# HandTieSchematic.net
KiCad netlist of a schematic drawn in Altium Designer
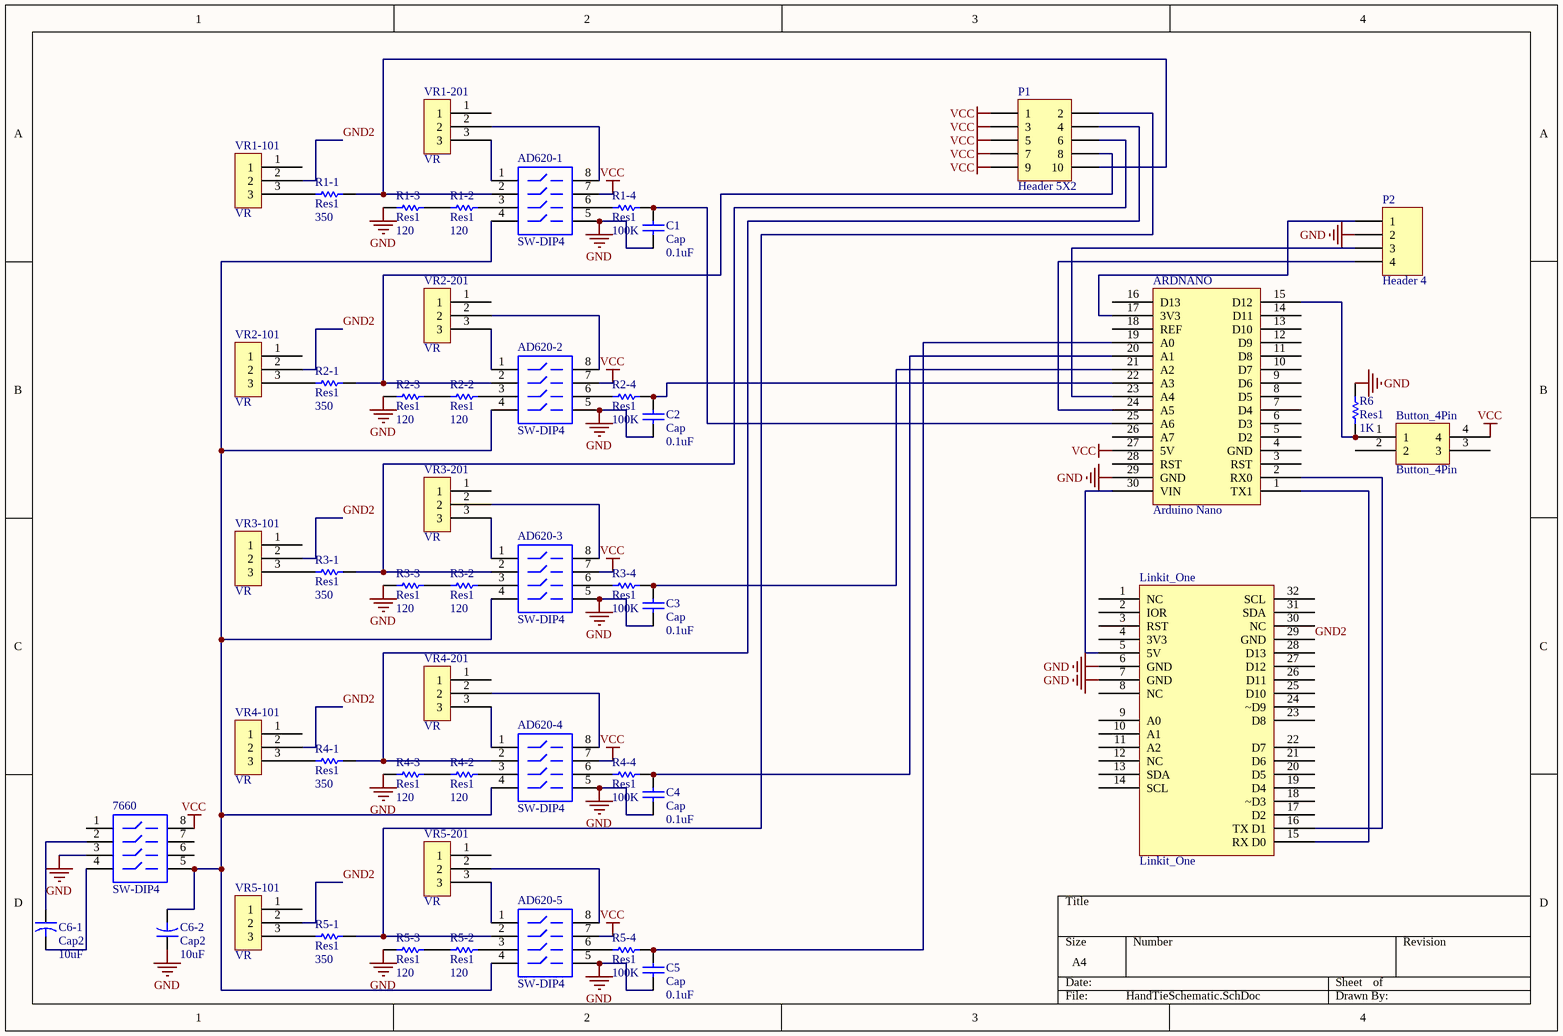
[diagram p0: HandTieSchematic.SchDoc]

(export (version "E")
  (design (tool "Eeschema 10.0.6"))
  (components
    (comp (ref "7660")
      (value "SW-DIP4")
      (footprint "DIP-8")
      (description "DIP Switch")
      (fields (field (name "PUBLISHER") "Altium Limited"))
      (libsource (lib "Miscellaneous Devices") (part "SW-DIP4"))
    )
    (comp (ref "AD620-1")
      (value "SW-DIP4")
      (footprint "DIP-8")
      (description "DIP Switch")
      (fields (field (name "PUBLISHER") "Altium Limited"))
      (libsource (lib "Miscellaneous Devices") (part "SW-DIP4"))
    )
    (comp (ref "AD620-2")
      (value "SW-DIP4")
      (footprint "DIP-8")
      (description "DIP Switch")
      (fields (field (name "PUBLISHER") "Altium Limited"))
      (libsource (lib "Miscellaneous Devices") (part "SW-DIP4"))
    )
    (comp (ref "AD620-3")
      (value "SW-DIP4")
      (footprint "DIP-8")
      (description "DIP Switch")
      (fields (field (name "PUBLISHER") "Altium Limited"))
      (libsource (lib "Miscellaneous Devices") (part "SW-DIP4"))
    )
    (comp (ref "AD620-4")
      (value "SW-DIP4")
      (footprint "DIP-8")
      (description "DIP Switch")
      (fields (field (name "PUBLISHER") "Altium Limited"))
      (libsource (lib "Miscellaneous Devices") (part "SW-DIP4"))
    )
    (comp (ref "AD620-5")
      (value "SW-DIP4")
      (footprint "DIP-8")
      (description "DIP Switch")
      (fields (field (name "PUBLISHER") "Altium Limited"))
      (libsource (lib "Miscellaneous Devices") (part "SW-DIP4"))
    )
    (comp (ref "ARDNANO")
      (value "Arduino Nano")
      (footprint "ARDNANO_DIP30")
      (libsource (lib "Arduino_Nano_Project") (part "Arduino Nano"))
    )
    (comp (ref "Button_4Pin")
      (value "Button_4Pin")
      (footprint "Button_4Pin")
      (libsource (lib "Button_4Pin_Project") (part "Button_4Pin"))
    )
    (comp (ref "C1")
      (value "Cap")
      (footprint "CAPR2.54-5.1x3.2")
      (description "Capacitor")
      (fields (field (name "ALTIUM_VALUE") "0.1uF") (field (name "PUBLISHER") "Altium Limited"))
      (libsource (lib "Miscellaneous Devices") (part "Cap"))
    )
    (comp (ref "C2")
      (value "Cap")
      (footprint "CAPR2.54-5.1x3.2")
      (description "Capacitor")
      (fields (field (name "ALTIUM_VALUE") "0.1uF") (field (name "PUBLISHER") "Altium Limited"))
      (libsource (lib "Miscellaneous Devices") (part "Cap"))
    )
    (comp (ref "C3")
      (value "Cap")
      (footprint "CAPR2.54-5.1x3.2")
      (description "Capacitor")
      (fields (field (name "ALTIUM_VALUE") "0.1uF") (field (name "PUBLISHER") "Altium Limited"))
      (libsource (lib "Miscellaneous Devices") (part "Cap"))
    )
    (comp (ref "C4")
      (value "Cap")
      (footprint "CAPR2.54-5.1x3.2")
      (description "Capacitor")
      (fields (field (name "ALTIUM_VALUE") "0.1uF") (field (name "PUBLISHER") "Altium Limited"))
      (libsource (lib "Miscellaneous Devices") (part "Cap"))
    )
    (comp (ref "C5")
      (value "Cap")
      (footprint "CAPR2.54-5.1x3.2")
      (description "Capacitor")
      (fields (field (name "ALTIUM_VALUE") "0.1uF") (field (name "PUBLISHER") "Altium Limited"))
      (libsource (lib "Miscellaneous Devices") (part "Cap"))
    )
    (comp (ref "C6-1")
      (value "Cap2")
      (footprint "CAPR5-4X5")
      (description "Capacitor")
      (fields (field (name "ALTIUM_VALUE") "10uF") (field (name "PUBLISHER") "Altium Limited"))
      (libsource (lib "Miscellaneous Devices") (part "Cap2"))
    )
    (comp (ref "C6-2")
      (value "Cap2")
      (footprint "CAPR5-4X5")
      (description "Capacitor")
      (fields (field (name "ALTIUM_VALUE") "10uF") (field (name "PUBLISHER") "Altium Limited"))
      (libsource (lib "Miscellaneous Devices") (part "Cap2"))
    )
    (comp (ref "Linkit_One")
      (value "Linkit_One")
      (footprint "Linkit_One")
      (libsource (lib "Linkit_One_Project") (part "Linkit_One"))
    )
    (comp (ref "P1")
      (value "Header 5X2")
      (footprint "HDR2X5")
      (description "Header, 5-Pin, Dual row")
      (fields (field (name "PUBLISHER") "Altium Limited"))
      (libsource (lib "Miscellaneous Connectors") (part "Header 5X2"))
    )
    (comp (ref "P2")
      (value "Header 4")
      (footprint "HDR1X4")
      (description "Header, 4-Pin")
      (fields (field (name "PUBLISHER") "Altium Limited"))
      (libsource (lib "Miscellaneous Connectors") (part "Header 4"))
    )
    (comp (ref "R1-1")
      (value "Res1")
      (footprint "AXIAL-0.3")
      (description "Resistor")
      (fields (field (name "ALTIUM_VALUE") "350") (field (name "PUBLISHER") "Altium Limited"))
      (libsource (lib "Miscellaneous Devices") (part "Res1"))
    )
    (comp (ref "R1-2")
      (value "Res1")
      (footprint "AXIAL-0.3")
      (description "Resistor")
      (fields (field (name "ALTIUM_VALUE") "120") (field (name "PUBLISHER") "Altium Limited"))
      (libsource (lib "Miscellaneous Devices") (part "Res1"))
    )
    (comp (ref "R1-3")
      (value "Res1")
      (footprint "AXIAL-0.3")
      (description "Resistor")
      (fields (field (name "ALTIUM_VALUE") "120") (field (name "PUBLISHER") "Altium Limited"))
      (libsource (lib "Miscellaneous Devices") (part "Res1"))
    )
    (comp (ref "R1-4")
      (value "Res1")
      (footprint "AXIAL-0.3")
      (description "Resistor")
      (fields (field (name "ALTIUM_VALUE") "100K") (field (name "PUBLISHER") "Altium Limited"))
      (libsource (lib "Miscellaneous Devices") (part "Res1"))
    )
    (comp (ref "R2-1")
      (value "Res1")
      (footprint "AXIAL-0.3")
      (description "Resistor")
      (fields (field (name "ALTIUM_VALUE") "350") (field (name "PUBLISHER") "Altium Limited"))
      (libsource (lib "Miscellaneous Devices") (part "Res1"))
    )
    (comp (ref "R2-2")
      (value "Res1")
      (footprint "AXIAL-0.3")
      (description "Resistor")
      (fields (field (name "ALTIUM_VALUE") "120") (field (name "PUBLISHER") "Altium Limited"))
      (libsource (lib "Miscellaneous Devices") (part "Res1"))
    )
    (comp (ref "R2-3")
      (value "Res1")
      (footprint "AXIAL-0.3")
      (description "Resistor")
      (fields (field (name "ALTIUM_VALUE") "120") (field (name "PUBLISHER") "Altium Limited"))
      (libsource (lib "Miscellaneous Devices") (part "Res1"))
    )
    (comp (ref "R2-4")
      (value "Res1")
      (footprint "AXIAL-0.3")
      (description "Resistor")
      (fields (field (name "ALTIUM_VALUE") "100K") (field (name "PUBLISHER") "Altium Limited"))
      (libsource (lib "Miscellaneous Devices") (part "Res1"))
    )
    (comp (ref "R3-1")
      (value "Res1")
      (footprint "AXIAL-0.3")
      (description "Resistor")
      (fields (field (name "ALTIUM_VALUE") "350") (field (name "PUBLISHER") "Altium Limited"))
      (libsource (lib "Miscellaneous Devices") (part "Res1"))
    )
    (comp (ref "R3-2")
      (value "Res1")
      (footprint "AXIAL-0.3")
      (description "Resistor")
      (fields (field (name "ALTIUM_VALUE") "120") (field (name "PUBLISHER") "Altium Limited"))
      (libsource (lib "Miscellaneous Devices") (part "Res1"))
    )
    (comp (ref "R3-3")
      (value "Res1")
      (footprint "AXIAL-0.3")
      (description "Resistor")
      (fields (field (name "ALTIUM_VALUE") "120") (field (name "PUBLISHER") "Altium Limited"))
      (libsource (lib "Miscellaneous Devices") (part "Res1"))
    )
    (comp (ref "R3-4")
      (value "Res1")
      (footprint "AXIAL-0.3")
      (description "Resistor")
      (fields (field (name "ALTIUM_VALUE") "100K") (field (name "PUBLISHER") "Altium Limited"))
      (libsource (lib "Miscellaneous Devices") (part "Res1"))
    )
    (comp (ref "R4-1")
      (value "Res1")
      (footprint "AXIAL-0.3")
      (description "Resistor")
      (fields (field (name "ALTIUM_VALUE") "350") (field (name "PUBLISHER") "Altium Limited"))
      (libsource (lib "Miscellaneous Devices") (part "Res1"))
    )
    (comp (ref "R4-2")
      (value "Res1")
      (footprint "AXIAL-0.3")
      (description "Resistor")
      (fields (field (name "ALTIUM_VALUE") "120") (field (name "PUBLISHER") "Altium Limited"))
      (libsource (lib "Miscellaneous Devices") (part "Res1"))
    )
    (comp (ref "R4-3")
      (value "Res1")
      (footprint "AXIAL-0.3")
      (description "Resistor")
      (fields (field (name "ALTIUM_VALUE") "120") (field (name "PUBLISHER") "Altium Limited"))
      (libsource (lib "Miscellaneous Devices") (part "Res1"))
    )
    (comp (ref "R4-4")
      (value "Res1")
      (footprint "AXIAL-0.3")
      (description "Resistor")
      (fields (field (name "ALTIUM_VALUE") "100K") (field (name "PUBLISHER") "Altium Limited"))
      (libsource (lib "Miscellaneous Devices") (part "Res1"))
    )
    (comp (ref "R5-1")
      (value "Res1")
      (footprint "AXIAL-0.3")
      (description "Resistor")
      (fields (field (name "ALTIUM_VALUE") "350") (field (name "PUBLISHER") "Altium Limited"))
      (libsource (lib "Miscellaneous Devices") (part "Res1"))
    )
    (comp (ref "R5-2")
      (value "Res1")
      (footprint "AXIAL-0.3")
      (description "Resistor")
      (fields (field (name "ALTIUM_VALUE") "120") (field (name "PUBLISHER") "Altium Limited"))
      (libsource (lib "Miscellaneous Devices") (part "Res1"))
    )
    (comp (ref "R5-3")
      (value "Res1")
      (footprint "AXIAL-0.3")
      (description "Resistor")
      (fields (field (name "ALTIUM_VALUE") "120") (field (name "PUBLISHER") "Altium Limited"))
      (libsource (lib "Miscellaneous Devices") (part "Res1"))
    )
    (comp (ref "R5-4")
      (value "Res1")
      (footprint "AXIAL-0.3")
      (description "Resistor")
      (fields (field (name "ALTIUM_VALUE") "100K") (field (name "PUBLISHER") "Altium Limited"))
      (libsource (lib "Miscellaneous Devices") (part "Res1"))
    )
    (comp (ref "R6")
      (value "Res1")
      (footprint "AXIAL-0.3")
      (description "Resistor")
      (fields (field (name "ALTIUM_VALUE") "1K") (field (name "PUBLISHER") "Altium Limited"))
      (libsource (lib "Miscellaneous Devices") (part "Res1"))
    )
    (comp (ref "VR1-101")
      (value "VR")
      (footprint "VarResistor")
      (libsource (lib "VariableResistor") (part "VarR"))
    )
    (comp (ref "VR1-201")
      (value "VR")
      (footprint "VarResistor")
      (libsource (lib "VariableResistor") (part "VarR"))
    )
    (comp (ref "VR2-101")
      (value "VR")
      (footprint "VarResistor")
      (libsource (lib "VariableResistor") (part "VarR"))
    )
    (comp (ref "VR2-201")
      (value "VR")
      (footprint "VarResistor")
      (libsource (lib "VariableResistor") (part "VarR"))
    )
    (comp (ref "VR3-101")
      (value "VR")
      (footprint "VarResistor")
      (libsource (lib "VariableResistor") (part "VarR"))
    )
    (comp (ref "VR3-201")
      (value "VR")
      (footprint "VarResistor")
      (libsource (lib "VariableResistor") (part "VarR"))
    )
    (comp (ref "VR4-101")
      (value "VR")
      (footprint "VarResistor")
      (libsource (lib "VariableResistor") (part "VarR"))
    )
    (comp (ref "VR4-201")
      (value "VR")
      (footprint "VarResistor")
      (libsource (lib "VariableResistor") (part "VarR"))
    )
    (comp (ref "VR5-101")
      (value "VR")
      (footprint "VarResistor")
      (libsource (lib "VariableResistor") (part "VarR"))
    )
    (comp (ref "VR5-201")
      (value "VR")
      (footprint "VarResistor")
      (libsource (lib "VariableResistor") (part "VarR"))
    )
  )
  (nets
    (net (code "1") (name "/GND2") (class "Default")
      (node (ref "Linkit_One") (pin "29") (pinfunction "GND_29") (pintype "passive"))
      (node (ref "VR1-101") (pin "2") (pinfunction "2_2") (pintype "passive"))
      (node (ref "VR2-101") (pin "2") (pinfunction "2_2") (pintype "passive"))
      (node (ref "VR3-101") (pin "2") (pinfunction "2_2") (pintype "passive"))
      (node (ref "VR4-101") (pin "2") (pinfunction "2_2") (pintype "passive"))
      (node (ref "VR5-101") (pin "2") (pinfunction "2_2") (pintype "passive"))
    )
    (net (code "2") (name "GND") (class "Default")
      (node (ref "7660") (pin "3") (pinfunction "3_3") (pintype "passive"))
      (node (ref "AD620-1") (pin "5") (pinfunction "5_5") (pintype "passive"))
      (node (ref "AD620-2") (pin "5") (pinfunction "5_5") (pintype "passive"))
      (node (ref "AD620-3") (pin "5") (pinfunction "5_5") (pintype "passive"))
      (node (ref "AD620-4") (pin "5") (pinfunction "5_5") (pintype "passive"))
      (node (ref "AD620-5") (pin "5") (pinfunction "5_5") (pintype "passive"))
      (node (ref "ARDNANO") (pin "29") (pinfunction "GND_29") (pintype "passive"))
      (node (ref "C1") (pin "2") (pinfunction "2_2") (pintype "passive"))
      (node (ref "C2") (pin "2") (pinfunction "2_2") (pintype "passive"))
      (node (ref "C3") (pin "2") (pinfunction "2_2") (pintype "passive"))
      (node (ref "C4") (pin "2") (pinfunction "2_2") (pintype "passive"))
      (node (ref "C5") (pin "2") (pinfunction "2_2") (pintype "passive"))
      (node (ref "C6-2") (pin "1") (pinfunction "1_1") (pintype "passive"))
      (node (ref "Linkit_One") (pin "6") (pinfunction "GND_6") (pintype "passive"))
      (node (ref "Linkit_One") (pin "7") (pinfunction "GND_7") (pintype "passive"))
      (node (ref "P2") (pin "2") (pinfunction "2_2") (pintype "passive"))
      (node (ref "R1-3") (pin "1") (pinfunction "1_1") (pintype "passive"))
      (node (ref "R2-3") (pin "1") (pinfunction "1_1") (pintype "passive"))
      (node (ref "R3-3") (pin "1") (pinfunction "1_1") (pintype "passive"))
      (node (ref "R4-3") (pin "1") (pinfunction "1_1") (pintype "passive"))
      (node (ref "R5-3") (pin "1") (pinfunction "1_1") (pintype "passive"))
      (node (ref "R6") (pin "2") (pinfunction "2_2") (pintype "passive"))
    )
    (net (code "3") (name "Net-(7660-Pad2)") (class "Default")
      (node (ref "7660") (pin "2") (pinfunction "2_2") (pintype "passive"))
      (node (ref "C6-1") (pin "1") (pinfunction "1_1") (pintype "passive"))
    )
    (net (code "4") (name "Net-(7660-Pad4)") (class "Default")
      (node (ref "7660") (pin "4") (pinfunction "4_4") (pintype "passive"))
      (node (ref "C6-1") (pin "2") (pinfunction "2_2") (pintype "passive"))
    )
    (net (code "5") (name "Net-(7660-Pad5)") (class "Default")
      (node (ref "7660") (pin "5") (pinfunction "5_5") (pintype "passive"))
      (node (ref "AD620-1") (pin "4") (pinfunction "4_4") (pintype "passive"))
      (node (ref "AD620-2") (pin "4") (pinfunction "4_4") (pintype "passive"))
      (node (ref "AD620-3") (pin "4") (pinfunction "4_4") (pintype "passive"))
      (node (ref "AD620-4") (pin "4") (pinfunction "4_4") (pintype "passive"))
      (node (ref "AD620-5") (pin "4") (pinfunction "4_4") (pintype "passive"))
      (node (ref "C6-2") (pin "2") (pinfunction "2_2") (pintype "passive"))
    )
    (net (code "6") (name "Net-(AD620-1-Pad1)") (class "Default")
      (node (ref "AD620-1") (pin "1") (pinfunction "1_1") (pintype "passive"))
      (node (ref "VR1-201") (pin "3") (pinfunction "3_3") (pintype "passive"))
    )
    (net (code "7") (name "Net-(AD620-1-Pad2)") (class "Default")
      (node (ref "AD620-1") (pin "2") (pinfunction "2_2") (pintype "passive"))
      (node (ref "P1") (pin "10") (pinfunction "10_10") (pintype "passive"))
      (node (ref "R1-1") (pin "2") (pinfunction "2_2") (pintype "passive"))
    )
    (net (code "8") (name "Net-(AD620-1-Pad3)") (class "Default")
      (node (ref "AD620-1") (pin "3") (pinfunction "3_3") (pintype "passive"))
      (node (ref "R1-2") (pin "2") (pinfunction "2_2") (pintype "passive"))
    )
    (net (code "9") (name "Net-(AD620-1-Pad6)") (class "Default")
      (node (ref "AD620-1") (pin "6") (pinfunction "6_6") (pintype "passive"))
      (node (ref "R1-4") (pin "2") (pinfunction "2_2") (pintype "passive"))
    )
    (net (code "10") (name "Net-(AD620-1-Pad8)") (class "Default")
      (node (ref "AD620-1") (pin "8") (pinfunction "8_8") (pintype "passive"))
      (node (ref "VR1-201") (pin "2") (pinfunction "2_2") (pintype "passive"))
    )
    (net (code "11") (name "Net-(AD620-2-Pad1)") (class "Default")
      (node (ref "AD620-2") (pin "1") (pinfunction "1_1") (pintype "passive"))
      (node (ref "VR2-201") (pin "3") (pinfunction "3_3") (pintype "passive"))
    )
    (net (code "12") (name "Net-(AD620-2-Pad2)") (class "Default")
      (node (ref "AD620-2") (pin "2") (pinfunction "2_2") (pintype "passive"))
      (node (ref "P1") (pin "8") (pinfunction "8_8") (pintype "passive"))
      (node (ref "R2-1") (pin "2") (pinfunction "2_2") (pintype "passive"))
    )
    (net (code "13") (name "Net-(AD620-2-Pad3)") (class "Default")
      (node (ref "AD620-2") (pin "3") (pinfunction "3_3") (pintype "passive"))
      (node (ref "R2-2") (pin "2") (pinfunction "2_2") (pintype "passive"))
    )
    (net (code "14") (name "Net-(AD620-2-Pad6)") (class "Default")
      (node (ref "AD620-2") (pin "6") (pinfunction "6_6") (pintype "passive"))
      (node (ref "R2-4") (pin "2") (pinfunction "2_2") (pintype "passive"))
    )
    (net (code "15") (name "Net-(AD620-2-Pad8)") (class "Default")
      (node (ref "AD620-2") (pin "8") (pinfunction "8_8") (pintype "passive"))
      (node (ref "VR2-201") (pin "2") (pinfunction "2_2") (pintype "passive"))
    )
    (net (code "16") (name "Net-(AD620-3-Pad1)") (class "Default")
      (node (ref "AD620-3") (pin "1") (pinfunction "1_1") (pintype "passive"))
      (node (ref "VR3-201") (pin "3") (pinfunction "3_3") (pintype "passive"))
    )
    (net (code "17") (name "Net-(AD620-3-Pad2)") (class "Default")
      (node (ref "AD620-3") (pin "2") (pinfunction "2_2") (pintype "passive"))
      (node (ref "P1") (pin "6") (pinfunction "6_6") (pintype "passive"))
      (node (ref "R3-1") (pin "2") (pinfunction "2_2") (pintype "passive"))
    )
    (net (code "18") (name "Net-(AD620-3-Pad3)") (class "Default")
      (node (ref "AD620-3") (pin "3") (pinfunction "3_3") (pintype "passive"))
      (node (ref "R3-2") (pin "2") (pinfunction "2_2") (pintype "passive"))
    )
    (net (code "19") (name "Net-(AD620-3-Pad6)") (class "Default")
      (node (ref "AD620-3") (pin "6") (pinfunction "6_6") (pintype "passive"))
      (node (ref "R3-4") (pin "2") (pinfunction "2_2") (pintype "passive"))
    )
    (net (code "20") (name "Net-(AD620-3-Pad8)") (class "Default")
      (node (ref "AD620-3") (pin "8") (pinfunction "8_8") (pintype "passive"))
      (node (ref "VR3-201") (pin "2") (pinfunction "2_2") (pintype "passive"))
    )
    (net (code "21") (name "Net-(AD620-4-Pad1)") (class "Default")
      (node (ref "AD620-4") (pin "1") (pinfunction "1_1") (pintype "passive"))
      (node (ref "VR4-201") (pin "3") (pinfunction "3_3") (pintype "passive"))
    )
    (net (code "22") (name "Net-(AD620-4-Pad2)") (class "Default")
      (node (ref "AD620-4") (pin "2") (pinfunction "2_2") (pintype "passive"))
      (node (ref "P1") (pin "4") (pinfunction "4_4") (pintype "passive"))
      (node (ref "R4-1") (pin "2") (pinfunction "2_2") (pintype "passive"))
    )
    (net (code "23") (name "Net-(AD620-4-Pad3)") (class "Default")
      (node (ref "AD620-4") (pin "3") (pinfunction "3_3") (pintype "passive"))
      (node (ref "R4-2") (pin "2") (pinfunction "2_2") (pintype "passive"))
    )
    (net (code "24") (name "Net-(AD620-4-Pad6)") (class "Default")
      (node (ref "AD620-4") (pin "6") (pinfunction "6_6") (pintype "passive"))
      (node (ref "R4-4") (pin "2") (pinfunction "2_2") (pintype "passive"))
    )
    (net (code "25") (name "Net-(AD620-4-Pad8)") (class "Default")
      (node (ref "AD620-4") (pin "8") (pinfunction "8_8") (pintype "passive"))
      (node (ref "VR4-201") (pin "2") (pinfunction "2_2") (pintype "passive"))
    )
    (net (code "26") (name "Net-(AD620-5-Pad1)") (class "Default")
      (node (ref "AD620-5") (pin "1") (pinfunction "1_1") (pintype "passive"))
      (node (ref "VR5-201") (pin "3") (pinfunction "3_3") (pintype "passive"))
    )
    (net (code "27") (name "Net-(AD620-5-Pad2)") (class "Default")
      (node (ref "AD620-5") (pin "2") (pinfunction "2_2") (pintype "passive"))
      (node (ref "P1") (pin "2") (pinfunction "2_2") (pintype "passive"))
      (node (ref "R5-1") (pin "2") (pinfunction "2_2") (pintype "passive"))
    )
    (net (code "28") (name "Net-(AD620-5-Pad3)") (class "Default")
      (node (ref "AD620-5") (pin "3") (pinfunction "3_3") (pintype "passive"))
      (node (ref "R5-2") (pin "2") (pinfunction "2_2") (pintype "passive"))
    )
    (net (code "29") (name "Net-(AD620-5-Pad6)") (class "Default")
      (node (ref "AD620-5") (pin "6") (pinfunction "6_6") (pintype "passive"))
      (node (ref "R5-4") (pin "2") (pinfunction "2_2") (pintype "passive"))
    )
    (net (code "30") (name "Net-(AD620-5-Pad8)") (class "Default")
      (node (ref "AD620-5") (pin "8") (pinfunction "8_8") (pintype "passive"))
      (node (ref "VR5-201") (pin "2") (pinfunction "2_2") (pintype "passive"))
    )
    (net (code "31") (name "Net-(ARDNANO-3V3)") (class "Default")
      (node (ref "ARDNANO") (pin "17") (pinfunction "3V3_17") (pintype "passive"))
      (node (ref "P2") (pin "1") (pinfunction "1_1") (pintype "passive"))
    )
    (net (code "32") (name "Net-(ARDNANO-A0)") (class "Default")
      (node (ref "ARDNANO") (pin "19") (pinfunction "A0_19") (pintype "passive"))
      (node (ref "C5") (pin "1") (pinfunction "1_1") (pintype "passive"))
      (node (ref "R5-4") (pin "1") (pinfunction "1_1") (pintype "passive"))
    )
    (net (code "33") (name "Net-(ARDNANO-A1)") (class "Default")
      (node (ref "ARDNANO") (pin "20") (pinfunction "A1_20") (pintype "passive"))
      (node (ref "C4") (pin "1") (pinfunction "1_1") (pintype "passive"))
      (node (ref "R4-4") (pin "1") (pinfunction "1_1") (pintype "passive"))
    )
    (net (code "34") (name "Net-(ARDNANO-A2)") (class "Default")
      (node (ref "ARDNANO") (pin "21") (pinfunction "A2_21") (pintype "passive"))
      (node (ref "C3") (pin "1") (pinfunction "1_1") (pintype "passive"))
      (node (ref "R3-4") (pin "1") (pinfunction "1_1") (pintype "passive"))
    )
    (net (code "35") (name "Net-(ARDNANO-A3)") (class "Default")
      (node (ref "ARDNANO") (pin "22") (pinfunction "A3_22") (pintype "passive"))
      (node (ref "C2") (pin "1") (pinfunction "1_1") (pintype "passive"))
      (node (ref "R2-4") (pin "1") (pinfunction "1_1") (pintype "passive"))
    )
    (net (code "36") (name "Net-(ARDNANO-A4)") (class "Default")
      (node (ref "ARDNANO") (pin "23") (pinfunction "A4_23") (pintype "passive"))
      (node (ref "P2") (pin "3") (pinfunction "3_3") (pintype "passive"))
    )
    (net (code "37") (name "Net-(ARDNANO-A5)") (class "Default")
      (node (ref "ARDNANO") (pin "24") (pinfunction "A5_24") (pintype "passive"))
      (node (ref "P2") (pin "4") (pinfunction "4_4") (pintype "passive"))
    )
    (net (code "38") (name "Net-(ARDNANO-A6)") (class "Default")
      (node (ref "ARDNANO") (pin "25") (pinfunction "A6_25") (pintype "passive"))
      (node (ref "C1") (pin "1") (pinfunction "1_1") (pintype "passive"))
      (node (ref "R1-4") (pin "1") (pinfunction "1_1") (pintype "passive"))
    )
    (net (code "39") (name "Net-(ARDNANO-D12)") (class "Default")
      (node (ref "ARDNANO") (pin "15") (pinfunction "D12_15") (pintype "passive"))
      (node (ref "Button_4Pin") (pin "1") (pinfunction "1_1") (pintype "passive"))
      (node (ref "R6") (pin "1") (pinfunction "1_1") (pintype "passive"))
    )
    (net (code "40") (name "Net-(ARDNANO-RX0)") (class "Default")
      (node (ref "ARDNANO") (pin "2") (pinfunction "RX0_2") (pintype "passive"))
      (node (ref "Linkit_One") (pin "16") (pinfunction "TX_D1_16") (pintype "passive"))
    )
    (net (code "41") (name "Net-(ARDNANO-TX1)") (class "Default")
      (node (ref "ARDNANO") (pin "1") (pinfunction "TX1_1") (pintype "passive"))
      (node (ref "Linkit_One") (pin "15") (pinfunction "RX_D0_15") (pintype "passive"))
    )
    (net (code "42") (name "Net-(ARDNANO-VIN)") (class "Default")
      (node (ref "ARDNANO") (pin "30") (pinfunction "VIN_30") (pintype "passive"))
      (node (ref "Linkit_One") (pin "5") (pinfunction "5V_5") (pintype "passive"))
    )
    (net (code "43") (name "Net-(R1-1-Pad1)") (class "Default")
      (node (ref "R1-1") (pin "1") (pinfunction "1_1") (pintype "passive"))
      (node (ref "VR1-101") (pin "3") (pinfunction "3_3") (pintype "passive"))
    )
    (net (code "44") (name "Net-(R1-2-Pad1)") (class "Default")
      (node (ref "R1-2") (pin "1") (pinfunction "1_1") (pintype "passive"))
      (node (ref "R1-3") (pin "2") (pinfunction "2_2") (pintype "passive"))
    )
    (net (code "45") (name "Net-(R2-1-Pad1)") (class "Default")
      (node (ref "R2-1") (pin "1") (pinfunction "1_1") (pintype "passive"))
      (node (ref "VR2-101") (pin "3") (pinfunction "3_3") (pintype "passive"))
    )
    (net (code "46") (name "Net-(R2-2-Pad1)") (class "Default")
      (node (ref "R2-2") (pin "1") (pinfunction "1_1") (pintype "passive"))
      (node (ref "R2-3") (pin "2") (pinfunction "2_2") (pintype "passive"))
    )
    (net (code "47") (name "Net-(R3-1-Pad1)") (class "Default")
      (node (ref "R3-1") (pin "1") (pinfunction "1_1") (pintype "passive"))
      (node (ref "VR3-101") (pin "3") (pinfunction "3_3") (pintype "passive"))
    )
    (net (code "48") (name "Net-(R3-2-Pad1)") (class "Default")
      (node (ref "R3-2") (pin "1") (pinfunction "1_1") (pintype "passive"))
      (node (ref "R3-3") (pin "2") (pinfunction "2_2") (pintype "passive"))
    )
    (net (code "49") (name "Net-(R4-1-Pad1)") (class "Default")
      (node (ref "R4-1") (pin "1") (pinfunction "1_1") (pintype "passive"))
      (node (ref "VR4-101") (pin "3") (pinfunction "3_3") (pintype "passive"))
    )
    (net (code "50") (name "Net-(R4-2-Pad1)") (class "Default")
      (node (ref "R4-2") (pin "1") (pinfunction "1_1") (pintype "passive"))
      (node (ref "R4-3") (pin "2") (pinfunction "2_2") (pintype "passive"))
    )
    (net (code "51") (name "Net-(R5-1-Pad1)") (class "Default")
      (node (ref "R5-1") (pin "1") (pinfunction "1_1") (pintype "passive"))
      (node (ref "VR5-101") (pin "3") (pinfunction "3_3") (pintype "passive"))
    )
    (net (code "52") (name "Net-(R5-2-Pad1)") (class "Default")
      (node (ref "R5-2") (pin "1") (pinfunction "1_1") (pintype "passive"))
      (node (ref "R5-3") (pin "2") (pinfunction "2_2") (pintype "passive"))
    )
    (net (code "53") (name "VCC") (class "Default")
      (node (ref "7660") (pin "8") (pinfunction "8_8") (pintype "passive"))
      (node (ref "AD620-1") (pin "7") (pinfunction "7_7") (pintype "passive"))
      (node (ref "AD620-2") (pin "7") (pinfunction "7_7") (pintype "passive"))
      (node (ref "AD620-3") (pin "7") (pinfunction "7_7") (pintype "passive"))
      (node (ref "AD620-4") (pin "7") (pinfunction "7_7") (pintype "passive"))
      (node (ref "AD620-5") (pin "7") (pinfunction "7_7") (pintype "passive"))
      (node (ref "ARDNANO") (pin "27") (pinfunction "5V_27") (pintype "passive"))
      (node (ref "Button_4Pin") (pin "4") (pinfunction "4_4") (pintype "passive"))
      (node (ref "P1") (pin "1") (pinfunction "1_1") (pintype "passive"))
      (node (ref "P1") (pin "3") (pinfunction "3_3") (pintype "passive"))
      (node (ref "P1") (pin "5") (pinfunction "5_5") (pintype "passive"))
      (node (ref "P1") (pin "7") (pinfunction "7_7") (pintype "passive"))
      (node (ref "P1") (pin "9") (pinfunction "9_9") (pintype "passive"))
    )
    (net (code "54") (name "unconnected-(7660-Pad1)") (class "Default")
      (node (ref "7660") (pin "1") (pinfunction "1_1") (pintype "passive"))
    )
    (net (code "55") (name "unconnected-(7660-Pad6)") (class "Default")
      (node (ref "7660") (pin "6") (pinfunction "6_6") (pintype "passive"))
    )
    (net (code "56") (name "unconnected-(7660-Pad7)") (class "Default")
      (node (ref "7660") (pin "7") (pinfunction "7_7") (pintype "passive"))
    )
    (net (code "57") (name "unconnected-(ARDNANO-A7-Pad26)") (class "Default")
      (node (ref "ARDNANO") (pin "26") (pinfunction "A7_26") (pintype "passive"))
    )
    (net (code "58") (name "unconnected-(ARDNANO-D2-Pad5)") (class "Default")
      (node (ref "ARDNANO") (pin "5") (pinfunction "D2_5") (pintype "passive"))
    )
    (net (code "59") (name "unconnected-(ARDNANO-D3-Pad6)") (class "Default")
      (node (ref "ARDNANO") (pin "6") (pinfunction "D3_6") (pintype "passive"))
    )
    (net (code "60") (name "unconnected-(ARDNANO-D4-Pad7)") (class "Default")
      (node (ref "ARDNANO") (pin "7") (pinfunction "D4_7") (pintype "passive"))
    )
    (net (code "61") (name "unconnected-(ARDNANO-D5-Pad8)") (class "Default")
      (node (ref "ARDNANO") (pin "8") (pinfunction "D5_8") (pintype "passive"))
    )
    (net (code "62") (name "unconnected-(ARDNANO-D6-Pad9)") (class "Default")
      (node (ref "ARDNANO") (pin "9") (pinfunction "D6_9") (pintype "passive"))
    )
    (net (code "63") (name "unconnected-(ARDNANO-D7-Pad10)") (class "Default")
      (node (ref "ARDNANO") (pin "10") (pinfunction "D7_10") (pintype "passive"))
    )
    (net (code "64") (name "unconnected-(ARDNANO-D8-Pad11)") (class "Default")
      (node (ref "ARDNANO") (pin "11") (pinfunction "D8_11") (pintype "passive"))
    )
    (net (code "65") (name "unconnected-(ARDNANO-D9-Pad12)") (class "Default")
      (node (ref "ARDNANO") (pin "12") (pinfunction "D9_12") (pintype "passive"))
    )
    (net (code "66") (name "unconnected-(ARDNANO-D10-Pad13)") (class "Default")
      (node (ref "ARDNANO") (pin "13") (pinfunction "D10_13") (pintype "passive"))
    )
    (net (code "67") (name "unconnected-(ARDNANO-D11-Pad14)") (class "Default")
      (node (ref "ARDNANO") (pin "14") (pinfunction "D11_14") (pintype "passive"))
    )
    (net (code "68") (name "unconnected-(ARDNANO-D13-Pad16)") (class "Default")
      (node (ref "ARDNANO") (pin "16") (pinfunction "D13_16") (pintype "passive"))
    )
    (net (code "69") (name "unconnected-(ARDNANO-GND-Pad4)") (class "Default")
      (node (ref "ARDNANO") (pin "4") (pinfunction "GND_4") (pintype "passive"))
    )
    (net (code "70") (name "unconnected-(ARDNANO-REF-Pad18)") (class "Default")
      (node (ref "ARDNANO") (pin "18") (pinfunction "REF_18") (pintype "passive"))
    )
    (net (code "71") (name "unconnected-(ARDNANO-RST-Pad3)") (class "Default")
      (node (ref "ARDNANO") (pin "3") (pinfunction "RST_3") (pintype "passive"))
    )
    (net (code "72") (name "unconnected-(ARDNANO-RST-Pad28)") (class "Default")
      (node (ref "ARDNANO") (pin "28") (pinfunction "RST_28") (pintype "passive"))
    )
    (net (code "73") (name "unconnected-(Button_4Pin-Pad2)") (class "Default")
      (node (ref "Button_4Pin") (pin "2") (pinfunction "2_2") (pintype "passive"))
    )
    (net (code "74") (name "unconnected-(Button_4Pin-Pad3)") (class "Default")
      (node (ref "Button_4Pin") (pin "3") (pinfunction "3_3") (pintype "passive"))
    )
    (net (code "75") (name "unconnected-(Linkit_One-3V3-Pad4)") (class "Default")
      (node (ref "Linkit_One") (pin "4") (pinfunction "3V3_4") (pintype "passive"))
    )
    (net (code "76") (name "unconnected-(Linkit_One-A0-Pad9)") (class "Default")
      (node (ref "Linkit_One") (pin "9") (pinfunction "A0_9") (pintype "passive"))
    )
    (net (code "77") (name "unconnected-(Linkit_One-A1-Pad10)") (class "Default")
      (node (ref "Linkit_One") (pin "10") (pinfunction "A1_10") (pintype "passive"))
    )
    (net (code "78") (name "unconnected-(Linkit_One-A2-Pad11)") (class "Default")
      (node (ref "Linkit_One") (pin "11") (pinfunction "A2_11") (pintype "passive"))
    )
    (net (code "79") (name "unconnected-(Linkit_One-D2-Pad17)") (class "Default")
      (node (ref "Linkit_One") (pin "17") (pinfunction "D2_17") (pintype "passive"))
    )
    (net (code "80") (name "unconnected-(Linkit_One-D4-Pad19)") (class "Default")
      (node (ref "Linkit_One") (pin "19") (pinfunction "D4_19") (pintype "passive"))
    )
    (net (code "81") (name "unconnected-(Linkit_One-D5-Pad20)") (class "Default")
      (node (ref "Linkit_One") (pin "20") (pinfunction "D5_20") (pintype "passive"))
    )
    (net (code "82") (name "unconnected-(Linkit_One-D6-Pad21)") (class "Default")
      (node (ref "Linkit_One") (pin "21") (pinfunction "D6_21") (pintype "passive"))
    )
    (net (code "83") (name "unconnected-(Linkit_One-D7-Pad22)") (class "Default")
      (node (ref "Linkit_One") (pin "22") (pinfunction "D7_22") (pintype "passive"))
    )
    (net (code "84") (name "unconnected-(Linkit_One-D8-Pad23)") (class "Default")
      (node (ref "Linkit_One") (pin "23") (pinfunction "D8_23") (pintype "passive"))
    )
    (net (code "85") (name "unconnected-(Linkit_One-D10-Pad25)") (class "Default")
      (node (ref "Linkit_One") (pin "25") (pinfunction "D10_25") (pintype "passive"))
    )
    (net (code "86") (name "unconnected-(Linkit_One-D11-Pad26)") (class "Default")
      (node (ref "Linkit_One") (pin "26") (pinfunction "D11_26") (pintype "passive"))
    )
    (net (code "87") (name "unconnected-(Linkit_One-D12-Pad27)") (class "Default")
      (node (ref "Linkit_One") (pin "27") (pinfunction "D12_27") (pintype "passive"))
    )
    (net (code "88") (name "unconnected-(Linkit_One-D13-Pad28)") (class "Default")
      (node (ref "Linkit_One") (pin "28") (pinfunction "D13_28") (pintype "passive"))
    )
    (net (code "89") (name "unconnected-(Linkit_One-IOR-Pad2)") (class "Default")
      (node (ref "Linkit_One") (pin "2") (pinfunction "IOR_2") (pintype "passive"))
    )
    (net (code "90") (name "unconnected-(Linkit_One-NC-Pad1)") (class "Default")
      (node (ref "Linkit_One") (pin "1") (pinfunction "NC_1") (pintype "passive"))
    )
    (net (code "91") (name "unconnected-(Linkit_One-NC-Pad8)") (class "Default")
      (node (ref "Linkit_One") (pin "8") (pinfunction "NC_8") (pintype "passive"))
    )
    (net (code "92") (name "unconnected-(Linkit_One-NC-Pad12)") (class "Default")
      (node (ref "Linkit_One") (pin "12") (pinfunction "NC_12") (pintype "passive"))
    )
    (net (code "93") (name "unconnected-(Linkit_One-NC-Pad30)") (class "Default")
      (node (ref "Linkit_One") (pin "30") (pinfunction "NC_30") (pintype "passive"))
    )
    (net (code "94") (name "unconnected-(Linkit_One-RST-Pad3)") (class "Default")
      (node (ref "Linkit_One") (pin "3") (pinfunction "RST_3") (pintype "passive"))
    )
    (net (code "95") (name "unconnected-(Linkit_One-SCL-Pad14)") (class "Default")
      (node (ref "Linkit_One") (pin "14") (pinfunction "SCL_14") (pintype "passive"))
    )
    (net (code "96") (name "unconnected-(Linkit_One-SCL-Pad32)") (class "Default")
      (node (ref "Linkit_One") (pin "32") (pinfunction "SCL_32") (pintype "passive"))
    )
    (net (code "97") (name "unconnected-(Linkit_One-SDA-Pad13)") (class "Default")
      (node (ref "Linkit_One") (pin "13") (pinfunction "SDA_13") (pintype "passive"))
    )
    (net (code "98") (name "unconnected-(Linkit_One-SDA-Pad31)") (class "Default")
      (node (ref "Linkit_One") (pin "31") (pinfunction "SDA_31") (pintype "passive"))
    )
    (net (code "99") (name "unconnected-(Linkit_One-~D3-Pad18)") (class "Default")
      (node (ref "Linkit_One") (pin "18") (pinfunction "~D3_18") (pintype "passive"))
    )
    (net (code "100") (name "unconnected-(Linkit_One-~D9-Pad24)") (class "Default")
      (node (ref "Linkit_One") (pin "24") (pinfunction "~D9_24") (pintype "passive"))
    )
    (net (code "101") (name "unconnected-(VR1-101-Pad1)") (class "Default")
      (node (ref "VR1-101") (pin "1") (pinfunction "1_1") (pintype "passive"))
    )
    (net (code "102") (name "unconnected-(VR1-201-Pad1)") (class "Default")
      (node (ref "VR1-201") (pin "1") (pinfunction "1_1") (pintype "passive"))
    )
    (net (code "103") (name "unconnected-(VR2-101-Pad1)") (class "Default")
      (node (ref "VR2-101") (pin "1") (pinfunction "1_1") (pintype "passive"))
    )
    (net (code "104") (name "unconnected-(VR2-201-Pad1)") (class "Default")
      (node (ref "VR2-201") (pin "1") (pinfunction "1_1") (pintype "passive"))
    )
    (net (code "105") (name "unconnected-(VR3-101-Pad1)") (class "Default")
      (node (ref "VR3-101") (pin "1") (pinfunction "1_1") (pintype "passive"))
    )
    (net (code "106") (name "unconnected-(VR3-201-Pad1)") (class "Default")
      (node (ref "VR3-201") (pin "1") (pinfunction "1_1") (pintype "passive"))
    )
    (net (code "107") (name "unconnected-(VR4-101-Pad1)") (class "Default")
      (node (ref "VR4-101") (pin "1") (pinfunction "1_1") (pintype "passive"))
    )
    (net (code "108") (name "unconnected-(VR4-201-Pad1)") (class "Default")
      (node (ref "VR4-201") (pin "1") (pinfunction "1_1") (pintype "passive"))
    )
    (net (code "109") (name "unconnected-(VR5-101-Pad1)") (class "Default")
      (node (ref "VR5-101") (pin "1") (pinfunction "1_1") (pintype "passive"))
    )
    (net (code "110") (name "unconnected-(VR5-201-Pad1)") (class "Default")
      (node (ref "VR5-201") (pin "1") (pinfunction "1_1") (pintype "passive"))
    )
  )
)
